# COBConnector.net
KiCad netlist of a schematic drawn in Altium Designer
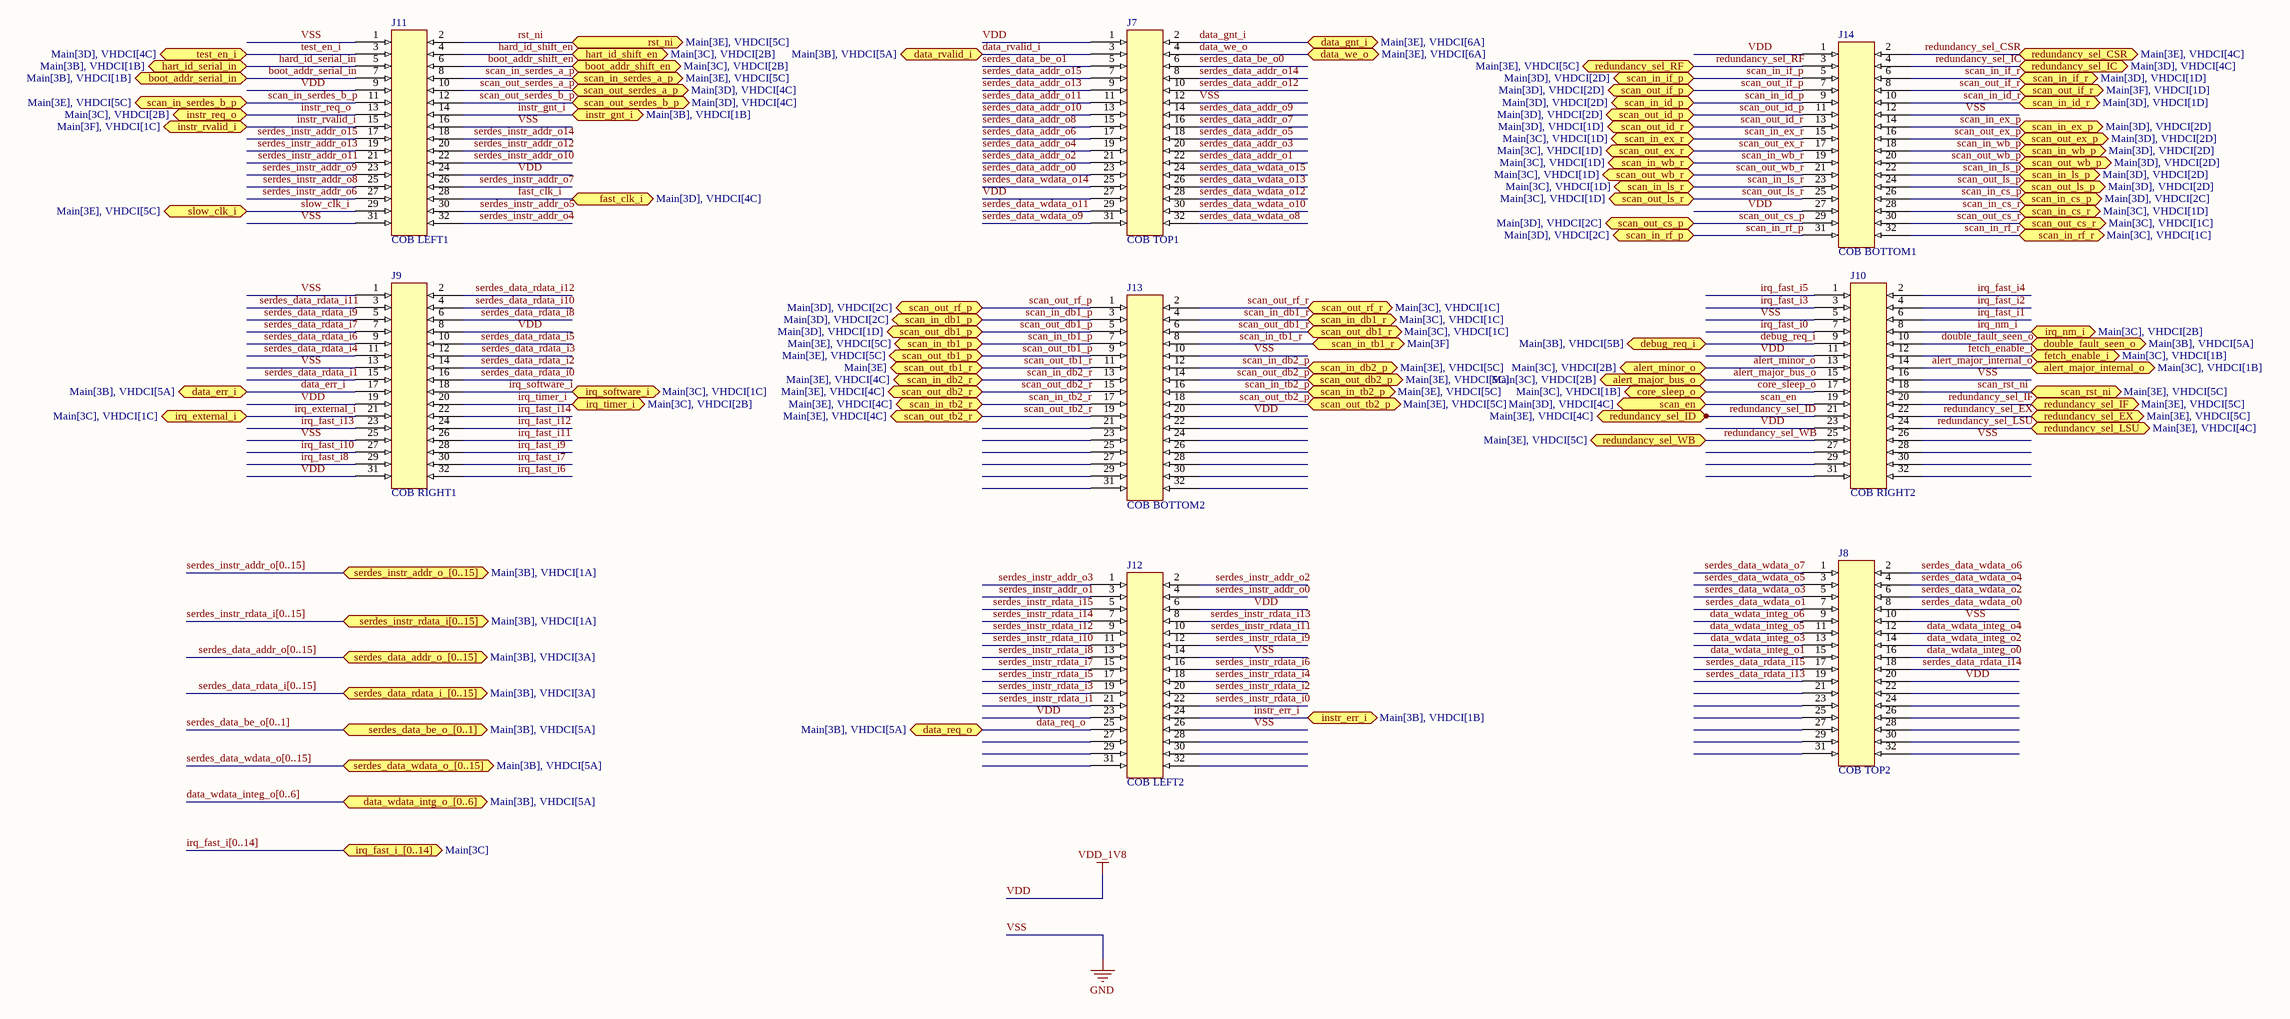
[diagram p0: COBConnector.SchDoc]

(export (version "E")
  (design (tool "Eeschema 10.0.6"))
  (components
    (comp (ref "J7")
      (value "COB TOP1")
      (footprint "CON32_2X16_TU_BBS_SAI")
      (libsource (lib "00-100001-001") (part "BBD-116-G-A"))
    )
    (comp (ref "J8")
      (value "COB TOP2")
      (footprint "CON32_2X16_TU_BBS_SAI")
      (libsource (lib "00-100001-001") (part "BBD-116-G-A"))
    )
    (comp (ref "J9")
      (value "COB RIGHT1")
      (footprint "CON32_2X16_TU_BBS_SAI")
      (libsource (lib "00-100001-001") (part "BBD-116-G-A"))
    )
    (comp (ref "J10")
      (value "COB RIGHT2")
      (footprint "CON32_2X16_TU_BBS_SAI")
      (libsource (lib "00-100001-001") (part "BBD-116-G-A"))
    )
    (comp (ref "J11")
      (value "COB LEFT1")
      (footprint "CON32_2X16_TU_BBS_SAI")
      (libsource (lib "00-100001-001") (part "BBD-116-G-A"))
    )
    (comp (ref "J12")
      (value "COB LEFT2")
      (footprint "CON32_2X16_TU_BBS_SAI")
      (libsource (lib "00-100001-001") (part "BBD-116-G-A"))
    )
    (comp (ref "J13")
      (value "COB BOTTOM2")
      (footprint "CON32_2X16_TU_BBS_SAI")
      (libsource (lib "00-100001-001") (part "BBD-116-G-A"))
    )
    (comp (ref "J14")
      (value "COB BOTTOM1")
      (footprint "CON32_2X16_TU_BBS_SAI")
      (libsource (lib "00-100001-001") (part "BBD-116-G-A"))
    )
  )
  (nets
    (net (code "1") (name "/alert_major_bus_o") (class "Default")
      (node (ref "J10") (pin "15") (pintype "input"))
    )
    (net (code "2") (name "/alert_major_internal_o") (class "Default")
      (node (ref "J10") (pin "14") (pintype "input"))
    )
    (net (code "3") (name "/alert_minor_o") (class "Default") (node (ref "J10") (pin "13") (pintype "input")))
    (net (code "4") (name "/boot_addr_serial_in") (class "Default")
      (node (ref "J11") (pin "7") (pintype "input"))
    )
    (net (code "5") (name "/boot_addr_shift_en") (class "Default")
      (node (ref "J11") (pin "6") (pintype "input"))
    )
    (net (code "6") (name "/core_sleep_o") (class "Default") (node (ref "J10") (pin "17") (pintype "input")))
    (net (code "7") (name "/data_err_i") (class "Default") (node (ref "J9") (pin "17") (pintype "input")))
    (net (code "8") (name "/data_gnt_i") (class "Default") (node (ref "J7") (pin "2") (pintype "input")))
    (net (code "9") (name "/data_req_o") (class "Default") (node (ref "J12") (pin "25") (pintype "input")))
    (net (code "10") (name "/data_rvalid_i") (class "Default") (node (ref "J7") (pin "3") (pintype "input")))
    (net (code "11") (name "/data_wdata_integ_o0") (class "Default")
      (node (ref "J8") (pin "16") (pintype "input"))
    )
    (net (code "12") (name "/data_wdata_integ_o1") (class "Default")
      (node (ref "J8") (pin "15") (pintype "input"))
    )
    (net (code "13") (name "/data_wdata_integ_o2") (class "Default")
      (node (ref "J8") (pin "14") (pintype "input"))
    )
    (net (code "14") (name "/data_wdata_integ_o3") (class "Default")
      (node (ref "J8") (pin "13") (pintype "input"))
    )
    (net (code "15") (name "/data_wdata_integ_o4") (class "Default")
      (node (ref "J8") (pin "12") (pintype "input"))
    )
    (net (code "16") (name "/data_wdata_integ_o5") (class "Default")
      (node (ref "J8") (pin "11") (pintype "input"))
    )
    (net (code "17") (name "/data_wdata_integ_o6") (class "Default")
      (node (ref "J8") (pin "9") (pintype "input"))
    )
    (net (code "19") (name "/data_we_o") (class "Default") (node (ref "J7") (pin "4") (pintype "input")))
    (net (code "20") (name "/debug_req_i") (class "Default") (node (ref "J10") (pin "9") (pintype "input")))
    (net (code "21") (name "/double_fault_seen_o") (class "Default")
      (node (ref "J10") (pin "10") (pintype "input"))
    )
    (net (code "22") (name "/fast_clk_i") (class "Default") (node (ref "J11") (pin "28") (pintype "input")))
    (net (code "23") (name "/fetch_enable_i") (class "Default")
      (node (ref "J10") (pin "12") (pintype "input"))
    )
    (net (code "24") (name "/hard_id_serial_in") (class "Default")
      (node (ref "J11") (pin "5") (pintype "input"))
    )
    (net (code "25") (name "/hard_id_shift_en") (class "Default")
      (node (ref "J11") (pin "4") (pintype "input"))
    )
    (net (code "26") (name "/instr_err_i") (class "Default") (node (ref "J12") (pin "24") (pintype "input")))
    (net (code "27") (name "/instr_gnt_i") (class "Default") (node (ref "J11") (pin "14") (pintype "input")))
    (net (code "28") (name "/instr_req_o") (class "Default") (node (ref "J11") (pin "13") (pintype "input")))
    (net (code "29") (name "/instr_rvalid_i") (class "Default")
      (node (ref "J11") (pin "15") (pintype "input"))
    )
    (net (code "30") (name "/irq_external_i") (class "Default")
      (node (ref "J9") (pin "21") (pintype "input"))
    )
    (net (code "31") (name "/irq_fast_i0") (class "Default") (node (ref "J10") (pin "7") (pintype "input")))
    (net (code "32") (name "/irq_fast_i1") (class "Default") (node (ref "J10") (pin "6") (pintype "input")))
    (net (code "33") (name "/irq_fast_i2") (class "Default") (node (ref "J10") (pin "4") (pintype "input")))
    (net (code "34") (name "/irq_fast_i3") (class "Default") (node (ref "J10") (pin "3") (pintype "input")))
    (net (code "35") (name "/irq_fast_i4") (class "Default") (node (ref "J10") (pin "2") (pintype "input")))
    (net (code "36") (name "/irq_fast_i5") (class "Default") (node (ref "J10") (pin "1") (pintype "input")))
    (net (code "37") (name "/irq_fast_i6") (class "Default") (node (ref "J9") (pin "32") (pintype "input")))
    (net (code "38") (name "/irq_fast_i7") (class "Default") (node (ref "J9") (pin "30") (pintype "input")))
    (net (code "39") (name "/irq_fast_i8") (class "Default") (node (ref "J9") (pin "29") (pintype "input")))
    (net (code "40") (name "/irq_fast_i9") (class "Default") (node (ref "J9") (pin "28") (pintype "input")))
    (net (code "41") (name "/irq_fast_i10") (class "Default") (node (ref "J9") (pin "27") (pintype "input")))
    (net (code "42") (name "/irq_fast_i11") (class "Default") (node (ref "J9") (pin "26") (pintype "input")))
    (net (code "43") (name "/irq_fast_i12") (class "Default") (node (ref "J9") (pin "24") (pintype "input")))
    (net (code "44") (name "/irq_fast_i13") (class "Default") (node (ref "J9") (pin "23") (pintype "input")))
    (net (code "45") (name "/irq_fast_i14") (class "Default") (node (ref "J9") (pin "22") (pintype "input")))
    (net (code "47") (name "/irq_nm_i") (class "Default") (node (ref "J10") (pin "8") (pintype "input")))
    (net (code "48") (name "/irq_software_i") (class "Default")
      (node (ref "J9") (pin "18") (pintype "input"))
    )
    (net (code "49") (name "/irq_timer_i") (class "Default") (node (ref "J9") (pin "20") (pintype "input")))
    (net (code "50") (name "/redundancy_sel_CSR") (class "Default")
      (node (ref "J14") (pin "2") (pintype "input"))
    )
    (net (code "51") (name "/redundancy_sel_EX") (class "Default")
      (node (ref "J10") (pin "22") (pintype "input"))
    )
    (net (code "52") (name "/redundancy_sel_IC") (class "Default")
      (node (ref "J14") (pin "4") (pintype "input"))
    )
    (net (code "53") (name "/redundancy_sel_ID") (class "Default")
      (node (ref "J10") (pin "21") (pintype "input"))
    )
    (net (code "54") (name "/redundancy_sel_IF") (class "Default")
      (node (ref "J10") (pin "20") (pintype "input"))
    )
    (net (code "55") (name "/redundancy_sel_LSU") (class "Default")
      (node (ref "J10") (pin "24") (pintype "input"))
    )
    (net (code "56") (name "/redundancy_sel_RF") (class "Default")
      (node (ref "J14") (pin "3") (pintype "input"))
    )
    (net (code "57") (name "/redundancy_sel_WB") (class "Default")
      (node (ref "J10") (pin "25") (pintype "input"))
    )
    (net (code "58") (name "/rst_ni") (class "Default") (node (ref "J11") (pin "2") (pintype "input")))
    (net (code "59") (name "/scan_en") (class "Default") (node (ref "J10") (pin "19") (pintype "input")))
    (net (code "60") (name "/scan_in_cs_p") (class "Default") (node (ref "J14") (pin "26") (pintype "input")))
    (net (code "61") (name "/scan_in_cs_r") (class "Default") (node (ref "J14") (pin "28") (pintype "input")))
    (net (code "62") (name "/scan_in_db1_p") (class "Default") (node (ref "J13") (pin "3") (pintype "input")))
    (net (code "63") (name "/scan_in_db1_r") (class "Default") (node (ref "J13") (pin "4") (pintype "input")))
    (net (code "64") (name "/scan_in_db2_p") (class "Default")
      (node (ref "J13") (pin "12") (pintype "input"))
    )
    (net (code "65") (name "/scan_in_db2_r") (class "Default")
      (node (ref "J13") (pin "13") (pintype "input"))
    )
    (net (code "66") (name "/scan_in_ex_p") (class "Default") (node (ref "J14") (pin "14") (pintype "input")))
    (net (code "67") (name "/scan_in_ex_r") (class "Default") (node (ref "J14") (pin "15") (pintype "input")))
    (net (code "68") (name "/scan_in_id_p") (class "Default") (node (ref "J14") (pin "9") (pintype "input")))
    (net (code "69") (name "/scan_in_id_r") (class "Default") (node (ref "J14") (pin "10") (pintype "input")))
    (net (code "70") (name "/scan_in_if_p") (class "Default") (node (ref "J14") (pin "5") (pintype "input")))
    (net (code "71") (name "/scan_in_if_r") (class "Default") (node (ref "J14") (pin "6") (pintype "input")))
    (net (code "72") (name "/scan_in_ls_p") (class "Default") (node (ref "J14") (pin "22") (pintype "input")))
    (net (code "73") (name "/scan_in_ls_r") (class "Default") (node (ref "J14") (pin "23") (pintype "input")))
    (net (code "74") (name "/scan_in_rf_p") (class "Default") (node (ref "J14") (pin "31") (pintype "input")))
    (net (code "75") (name "/scan_in_rf_r") (class "Default") (node (ref "J14") (pin "32") (pintype "input")))
    (net (code "76") (name "/scan_in_serdes_a_p") (class "Default")
      (node (ref "J11") (pin "8") (pintype "input"))
    )
    (net (code "77") (name "/scan_in_serdes_b_p") (class "Default")
      (node (ref "J11") (pin "11") (pintype "input"))
    )
    (net (code "78") (name "/scan_in_tb1_p") (class "Default") (node (ref "J13") (pin "7") (pintype "input")))
    (net (code "79") (name "/scan_in_tb1_r") (class "Default") (node (ref "J13") (pin "8") (pintype "input")))
    (net (code "80") (name "/scan_in_tb2_p") (class "Default")
      (node (ref "J13") (pin "16") (pintype "input"))
    )
    (net (code "81") (name "/scan_in_tb2_r") (class "Default")
      (node (ref "J13") (pin "17") (pintype "input"))
    )
    (net (code "82") (name "/scan_in_wb_p") (class "Default") (node (ref "J14") (pin "18") (pintype "input")))
    (net (code "83") (name "/scan_in_wb_r") (class "Default") (node (ref "J14") (pin "19") (pintype "input")))
    (net (code "84") (name "/scan_out_cs_p") (class "Default")
      (node (ref "J14") (pin "29") (pintype "input"))
    )
    (net (code "85") (name "/scan_out_cs_r") (class "Default")
      (node (ref "J14") (pin "30") (pintype "input"))
    )
    (net (code "86") (name "/scan_out_db1_p") (class "Default")
      (node (ref "J13") (pin "5") (pintype "input"))
    )
    (net (code "87") (name "/scan_out_db1_r") (class "Default")
      (node (ref "J13") (pin "6") (pintype "input"))
    )
    (net (code "88") (name "/scan_out_db2_p") (class "Default")
      (node (ref "J13") (pin "14") (pintype "input"))
    )
    (net (code "89") (name "/scan_out_db2_r") (class "Default")
      (node (ref "J13") (pin "15") (pintype "input"))
    )
    (net (code "90") (name "/scan_out_ex_p") (class "Default")
      (node (ref "J14") (pin "16") (pintype "input"))
    )
    (net (code "91") (name "/scan_out_ex_r") (class "Default")
      (node (ref "J14") (pin "17") (pintype "input"))
    )
    (net (code "92") (name "/scan_out_id_p") (class "Default")
      (node (ref "J14") (pin "11") (pintype "input"))
    )
    (net (code "93") (name "/scan_out_id_r") (class "Default")
      (node (ref "J14") (pin "13") (pintype "input"))
    )
    (net (code "94") (name "/scan_out_if_p") (class "Default") (node (ref "J14") (pin "7") (pintype "input")))
    (net (code "95") (name "/scan_out_if_r") (class "Default") (node (ref "J14") (pin "8") (pintype "input")))
    (net (code "96") (name "/scan_out_ls_p") (class "Default")
      (node (ref "J14") (pin "24") (pintype "input"))
    )
    (net (code "97") (name "/scan_out_ls_r") (class "Default")
      (node (ref "J14") (pin "25") (pintype "input"))
    )
    (net (code "98") (name "/scan_out_rf_p") (class "Default") (node (ref "J13") (pin "1") (pintype "input")))
    (net (code "99") (name "/scan_out_rf_r") (class "Default") (node (ref "J13") (pin "2") (pintype "input")))
    (net (code "100") (name "/scan_out_serdes_a_p") (class "Default")
      (node (ref "J11") (pin "10") (pintype "input"))
    )
    (net (code "101") (name "/scan_out_serdes_b_p") (class "Default")
      (node (ref "J11") (pin "12") (pintype "input"))
    )
    (net (code "102") (name "/scan_out_tb1_p") (class "Default")
      (node (ref "J13") (pin "9") (pintype "input"))
    )
    (net (code "103") (name "/scan_out_tb1_r") (class "Default")
      (node (ref "J13") (pin "11") (pintype "input"))
    )
    (net (code "104") (name "/scan_out_tb2_p") (class "Default")
      (node (ref "J13") (pin "18") (pintype "input"))
    )
    (net (code "105") (name "/scan_out_tb2_r") (class "Default")
      (node (ref "J13") (pin "19") (pintype "input"))
    )
    (net (code "106") (name "/scan_out_wb_p") (class "Default")
      (node (ref "J14") (pin "20") (pintype "input"))
    )
    (net (code "107") (name "/scan_out_wb_r") (class "Default")
      (node (ref "J14") (pin "21") (pintype "input"))
    )
    (net (code "108") (name "/scan_rst_ni") (class "Default") (node (ref "J10") (pin "18") (pintype "input")))
    (net (code "109") (name "/serdes_data_addr_o0") (class "Default")
      (node (ref "J7") (pin "23") (pintype "input"))
    )
    (net (code "110") (name "/serdes_data_addr_o1") (class "Default")
      (node (ref "J7") (pin "22") (pintype "input"))
    )
    (net (code "111") (name "/serdes_data_addr_o2") (class "Default")
      (node (ref "J7") (pin "21") (pintype "input"))
    )
    (net (code "112") (name "/serdes_data_addr_o3") (class "Default")
      (node (ref "J7") (pin "20") (pintype "input"))
    )
    (net (code "113") (name "/serdes_data_addr_o4") (class "Default")
      (node (ref "J7") (pin "19") (pintype "input"))
    )
    (net (code "114") (name "/serdes_data_addr_o5") (class "Default")
      (node (ref "J7") (pin "18") (pintype "input"))
    )
    (net (code "115") (name "/serdes_data_addr_o6") (class "Default")
      (node (ref "J7") (pin "17") (pintype "input"))
    )
    (net (code "116") (name "/serdes_data_addr_o7") (class "Default")
      (node (ref "J7") (pin "16") (pintype "input"))
    )
    (net (code "117") (name "/serdes_data_addr_o8") (class "Default")
      (node (ref "J7") (pin "15") (pintype "input"))
    )
    (net (code "118") (name "/serdes_data_addr_o9") (class "Default")
      (node (ref "J7") (pin "14") (pintype "input"))
    )
    (net (code "119") (name "/serdes_data_addr_o10") (class "Default")
      (node (ref "J7") (pin "13") (pintype "input"))
    )
    (net (code "120") (name "/serdes_data_addr_o11") (class "Default")
      (node (ref "J7") (pin "11") (pintype "input"))
    )
    (net (code "121") (name "/serdes_data_addr_o12") (class "Default")
      (node (ref "J7") (pin "10") (pintype "input"))
    )
    (net (code "122") (name "/serdes_data_addr_o13") (class "Default")
      (node (ref "J7") (pin "9") (pintype "input"))
    )
    (net (code "123") (name "/serdes_data_addr_o14") (class "Default")
      (node (ref "J7") (pin "8") (pintype "input"))
    )
    (net (code "124") (name "/serdes_data_addr_o15") (class "Default")
      (node (ref "J7") (pin "7") (pintype "input"))
    )
    (net (code "126") (name "/serdes_data_be_o0") (class "Default")
      (node (ref "J7") (pin "6") (pintype "input"))
    )
    (net (code "127") (name "/serdes_data_be_o1") (class "Default")
      (node (ref "J7") (pin "5") (pintype "input"))
    )
    (net (code "129") (name "/serdes_data_rdata_i0") (class "Default")
      (node (ref "J9") (pin "16") (pintype "input"))
    )
    (net (code "130") (name "/serdes_data_rdata_i1") (class "Default")
      (node (ref "J9") (pin "15") (pintype "input"))
    )
    (net (code "131") (name "/serdes_data_rdata_i2") (class "Default")
      (node (ref "J9") (pin "14") (pintype "input"))
    )
    (net (code "132") (name "/serdes_data_rdata_i3") (class "Default")
      (node (ref "J9") (pin "12") (pintype "input"))
    )
    (net (code "133") (name "/serdes_data_rdata_i4") (class "Default")
      (node (ref "J9") (pin "11") (pintype "input"))
    )
    (net (code "134") (name "/serdes_data_rdata_i5") (class "Default")
      (node (ref "J9") (pin "10") (pintype "input"))
    )
    (net (code "135") (name "/serdes_data_rdata_i6") (class "Default")
      (node (ref "J9") (pin "9") (pintype "input"))
    )
    (net (code "136") (name "/serdes_data_rdata_i7") (class "Default")
      (node (ref "J9") (pin "7") (pintype "input"))
    )
    (net (code "137") (name "/serdes_data_rdata_i8") (class "Default")
      (node (ref "J9") (pin "6") (pintype "input"))
    )
    (net (code "138") (name "/serdes_data_rdata_i9") (class "Default")
      (node (ref "J9") (pin "5") (pintype "input"))
    )
    (net (code "139") (name "/serdes_data_rdata_i10") (class "Default")
      (node (ref "J9") (pin "4") (pintype "input"))
    )
    (net (code "140") (name "/serdes_data_rdata_i11") (class "Default")
      (node (ref "J9") (pin "3") (pintype "input"))
    )
    (net (code "141") (name "/serdes_data_rdata_i12") (class "Default")
      (node (ref "J9") (pin "2") (pintype "input"))
    )
    (net (code "142") (name "/serdes_data_rdata_i13") (class "Default")
      (node (ref "J8") (pin "19") (pintype "input"))
    )
    (net (code "143") (name "/serdes_data_rdata_i14") (class "Default")
      (node (ref "J8") (pin "18") (pintype "input"))
    )
    (net (code "144") (name "/serdes_data_rdata_i15") (class "Default")
      (node (ref "J8") (pin "17") (pintype "input"))
    )
    (net (code "146") (name "/serdes_data_wdata_o0") (class "Default")
      (node (ref "J8") (pin "8") (pintype "input"))
    )
    (net (code "147") (name "/serdes_data_wdata_o1") (class "Default")
      (node (ref "J8") (pin "7") (pintype "input"))
    )
    (net (code "148") (name "/serdes_data_wdata_o2") (class "Default")
      (node (ref "J8") (pin "6") (pintype "input"))
    )
    (net (code "149") (name "/serdes_data_wdata_o3") (class "Default")
      (node (ref "J8") (pin "5") (pintype "input"))
    )
    (net (code "150") (name "/serdes_data_wdata_o4") (class "Default")
      (node (ref "J8") (pin "4") (pintype "input"))
    )
    (net (code "151") (name "/serdes_data_wdata_o5") (class "Default")
      (node (ref "J8") (pin "3") (pintype "input"))
    )
    (net (code "152") (name "/serdes_data_wdata_o6") (class "Default")
      (node (ref "J8") (pin "2") (pintype "input"))
    )
    (net (code "153") (name "/serdes_data_wdata_o7") (class "Default")
      (node (ref "J8") (pin "1") (pintype "input"))
    )
    (net (code "154") (name "/serdes_data_wdata_o8") (class "Default")
      (node (ref "J7") (pin "32") (pintype "input"))
    )
    (net (code "155") (name "/serdes_data_wdata_o9") (class "Default")
      (node (ref "J7") (pin "31") (pintype "input"))
    )
    (net (code "156") (name "/serdes_data_wdata_o10") (class "Default")
      (node (ref "J7") (pin "30") (pintype "input"))
    )
    (net (code "157") (name "/serdes_data_wdata_o11") (class "Default")
      (node (ref "J7") (pin "29") (pintype "input"))
    )
    (net (code "158") (name "/serdes_data_wdata_o12") (class "Default")
      (node (ref "J7") (pin "28") (pintype "input"))
    )
    (net (code "159") (name "/serdes_data_wdata_o13") (class "Default")
      (node (ref "J7") (pin "26") (pintype "input"))
    )
    (net (code "160") (name "/serdes_data_wdata_o14") (class "Default")
      (node (ref "J7") (pin "25") (pintype "input"))
    )
    (net (code "161") (name "/serdes_data_wdata_o15") (class "Default")
      (node (ref "J7") (pin "24") (pintype "input"))
    )
    (net (code "163") (name "/serdes_instr_addr_o0") (class "Default")
      (node (ref "J12") (pin "4") (pintype "input"))
    )
    (net (code "164") (name "/serdes_instr_addr_o1") (class "Default")
      (node (ref "J12") (pin "3") (pintype "input"))
    )
    (net (code "165") (name "/serdes_instr_addr_o2") (class "Default")
      (node (ref "J12") (pin "2") (pintype "input"))
    )
    (net (code "166") (name "/serdes_instr_addr_o3") (class "Default")
      (node (ref "J12") (pin "1") (pintype "input"))
    )
    (net (code "167") (name "/serdes_instr_addr_o4") (class "Default")
      (node (ref "J11") (pin "32") (pintype "input"))
    )
    (net (code "168") (name "/serdes_instr_addr_o5") (class "Default")
      (node (ref "J11") (pin "30") (pintype "input"))
    )
    (net (code "169") (name "/serdes_instr_addr_o6") (class "Default")
      (node (ref "J11") (pin "27") (pintype "input"))
    )
    (net (code "170") (name "/serdes_instr_addr_o7") (class "Default")
      (node (ref "J11") (pin "26") (pintype "input"))
    )
    (net (code "171") (name "/serdes_instr_addr_o8") (class "Default")
      (node (ref "J11") (pin "25") (pintype "input"))
    )
    (net (code "172") (name "/serdes_instr_addr_o9") (class "Default")
      (node (ref "J11") (pin "23") (pintype "input"))
    )
    (net (code "173") (name "/serdes_instr_addr_o10") (class "Default")
      (node (ref "J11") (pin "22") (pintype "input"))
    )
    (net (code "174") (name "/serdes_instr_addr_o11") (class "Default")
      (node (ref "J11") (pin "21") (pintype "input"))
    )
    (net (code "175") (name "/serdes_instr_addr_o12") (class "Default")
      (node (ref "J11") (pin "20") (pintype "input"))
    )
    (net (code "176") (name "/serdes_instr_addr_o13") (class "Default")
      (node (ref "J11") (pin "19") (pintype "input"))
    )
    (net (code "177") (name "/serdes_instr_addr_o14") (class "Default")
      (node (ref "J11") (pin "18") (pintype "input"))
    )
    (net (code "178") (name "/serdes_instr_addr_o15") (class "Default")
      (node (ref "J11") (pin "17") (pintype "input"))
    )
    (net (code "180") (name "/serdes_instr_rdata_i0") (class "Default")
      (node (ref "J12") (pin "22") (pintype "input"))
    )
    (net (code "181") (name "/serdes_instr_rdata_i1") (class "Default")
      (node (ref "J12") (pin "21") (pintype "input"))
    )
    (net (code "182") (name "/serdes_instr_rdata_i2") (class "Default")
      (node (ref "J12") (pin "20") (pintype "input"))
    )
    (net (code "183") (name "/serdes_instr_rdata_i3") (class "Default")
      (node (ref "J12") (pin "19") (pintype "input"))
    )
    (net (code "184") (name "/serdes_instr_rdata_i4") (class "Default")
      (node (ref "J12") (pin "18") (pintype "input"))
    )
    (net (code "185") (name "/serdes_instr_rdata_i5") (class "Default")
      (node (ref "J12") (pin "17") (pintype "input"))
    )
    (net (code "186") (name "/serdes_instr_rdata_i6") (class "Default")
      (node (ref "J12") (pin "16") (pintype "input"))
    )
    (net (code "187") (name "/serdes_instr_rdata_i7") (class "Default")
      (node (ref "J12") (pin "15") (pintype "input"))
    )
    (net (code "188") (name "/serdes_instr_rdata_i8") (class "Default")
      (node (ref "J12") (pin "13") (pintype "input"))
    )
    (net (code "189") (name "/serdes_instr_rdata_i9") (class "Default")
      (node (ref "J12") (pin "12") (pintype "input"))
    )
    (net (code "190") (name "/serdes_instr_rdata_i10") (class "Default")
      (node (ref "J12") (pin "11") (pintype "input"))
    )
    (net (code "191") (name "/serdes_instr_rdata_i11") (class "Default")
      (node (ref "J12") (pin "10") (pintype "input"))
    )
    (net (code "192") (name "/serdes_instr_rdata_i12") (class "Default")
      (node (ref "J12") (pin "9") (pintype "input"))
    )
    (net (code "193") (name "/serdes_instr_rdata_i13") (class "Default")
      (node (ref "J12") (pin "8") (pintype "input"))
    )
    (net (code "194") (name "/serdes_instr_rdata_i14") (class "Default")
      (node (ref "J12") (pin "7") (pintype "input"))
    )
    (net (code "195") (name "/serdes_instr_rdata_i15") (class "Default")
      (node (ref "J12") (pin "5") (pintype "input"))
    )
    (net (code "197") (name "/slow_clk_i") (class "Default") (node (ref "J11") (pin "29") (pintype "input")))
    (net (code "198") (name "/test_en_i") (class "Default") (node (ref "J11") (pin "3") (pintype "input")))
    (net (code "199") (name "GND") (class "Default")
      (node (ref "J10") (pin "16") (pintype "input"))
      (node (ref "J10") (pin "26") (pintype "input"))
      (node (ref "J10") (pin "5") (pintype "input"))
      (node (ref "J11") (pin "1") (pintype "input"))
      (node (ref "J11") (pin "16") (pintype "input"))
      (node (ref "J11") (pin "31") (pintype "input"))
      (node (ref "J12") (pin "14") (pintype "input"))
      (node (ref "J12") (pin "26") (pintype "input"))
      (node (ref "J13") (pin "10") (pintype "input"))
      (node (ref "J14") (pin "12") (pintype "input"))
      (node (ref "J7") (pin "12") (pintype "input"))
      (node (ref "J8") (pin "10") (pintype "input"))
      (node (ref "J9") (pin "1") (pintype "input"))
      (node (ref "J9") (pin "13") (pintype "input"))
      (node (ref "J9") (pin "25") (pintype "input"))
    )
    (net (code "200") (name "VDD_1V8") (class "Default")
      (node (ref "J10") (pin "11") (pintype "input"))
      (node (ref "J10") (pin "23") (pintype "input"))
      (node (ref "J11") (pin "24") (pintype "input"))
      (node (ref "J11") (pin "9") (pintype "input"))
      (node (ref "J12") (pin "23") (pintype "input"))
      (node (ref "J12") (pin "6") (pintype "input"))
      (node (ref "J13") (pin "20") (pintype "input"))
      (node (ref "J14") (pin "1") (pintype "input"))
      (node (ref "J14") (pin "27") (pintype "input"))
      (node (ref "J7") (pin "1") (pintype "input"))
      (node (ref "J7") (pin "27") (pintype "input"))
      (node (ref "J8") (pin "20") (pintype "input"))
      (node (ref "J9") (pin "19") (pintype "input"))
      (node (ref "J9") (pin "31") (pintype "input"))
      (node (ref "J9") (pin "8") (pintype "input"))
    )
    (net (code "201") (name "unconnected-(J8-Pad21)") (class "Default")
      (node (ref "J8") (pin "21") (pintype "input"))
    )
    (net (code "202") (name "unconnected-(J8-Pad22)") (class "Default")
      (node (ref "J8") (pin "22") (pintype "input"))
    )
    (net (code "203") (name "unconnected-(J8-Pad23)") (class "Default")
      (node (ref "J8") (pin "23") (pintype "input"))
    )
    (net (code "204") (name "unconnected-(J8-Pad24)") (class "Default")
      (node (ref "J8") (pin "24") (pintype "input"))
    )
    (net (code "205") (name "unconnected-(J8-Pad25)") (class "Default")
      (node (ref "J8") (pin "25") (pintype "input"))
    )
    (net (code "206") (name "unconnected-(J8-Pad26)") (class "Default")
      (node (ref "J8") (pin "26") (pintype "input"))
    )
    (net (code "207") (name "unconnected-(J8-Pad27)") (class "Default")
      (node (ref "J8") (pin "27") (pintype "input"))
    )
    (net (code "208") (name "unconnected-(J8-Pad28)") (class "Default")
      (node (ref "J8") (pin "28") (pintype "input"))
    )
    (net (code "209") (name "unconnected-(J8-Pad29)") (class "Default")
      (node (ref "J8") (pin "29") (pintype "input"))
    )
    (net (code "210") (name "unconnected-(J8-Pad30)") (class "Default")
      (node (ref "J8") (pin "30") (pintype "input"))
    )
    (net (code "211") (name "unconnected-(J8-Pad31)") (class "Default")
      (node (ref "J8") (pin "31") (pintype "input"))
    )
    (net (code "212") (name "unconnected-(J8-Pad32)") (class "Default")
      (node (ref "J8") (pin "32") (pintype "input"))
    )
    (net (code "213") (name "unconnected-(J10-Pad27)") (class "Default")
      (node (ref "J10") (pin "27") (pintype "input"))
    )
    (net (code "214") (name "unconnected-(J10-Pad28)") (class "Default")
      (node (ref "J10") (pin "28") (pintype "input"))
    )
    (net (code "215") (name "unconnected-(J10-Pad29)") (class "Default")
      (node (ref "J10") (pin "29") (pintype "input"))
    )
    (net (code "216") (name "unconnected-(J10-Pad30)") (class "Default")
      (node (ref "J10") (pin "30") (pintype "input"))
    )
    (net (code "217") (name "unconnected-(J10-Pad31)") (class "Default")
      (node (ref "J10") (pin "31") (pintype "input"))
    )
    (net (code "218") (name "unconnected-(J10-Pad32)") (class "Default")
      (node (ref "J10") (pin "32") (pintype "input"))
    )
    (net (code "219") (name "unconnected-(J12-Pad27)") (class "Default")
      (node (ref "J12") (pin "27") (pintype "input"))
    )
    (net (code "220") (name "unconnected-(J12-Pad28)") (class "Default")
      (node (ref "J12") (pin "28") (pintype "input"))
    )
    (net (code "221") (name "unconnected-(J12-Pad29)") (class "Default")
      (node (ref "J12") (pin "29") (pintype "input"))
    )
    (net (code "222") (name "unconnected-(J12-Pad30)") (class "Default")
      (node (ref "J12") (pin "30") (pintype "input"))
    )
    (net (code "223") (name "unconnected-(J12-Pad31)") (class "Default")
      (node (ref "J12") (pin "31") (pintype "input"))
    )
    (net (code "224") (name "unconnected-(J12-Pad32)") (class "Default")
      (node (ref "J12") (pin "32") (pintype "input"))
    )
    (net (code "225") (name "unconnected-(J13-Pad21)") (class "Default")
      (node (ref "J13") (pin "21") (pintype "input"))
    )
    (net (code "226") (name "unconnected-(J13-Pad22)") (class "Default")
      (node (ref "J13") (pin "22") (pintype "input"))
    )
    (net (code "227") (name "unconnected-(J13-Pad23)") (class "Default")
      (node (ref "J13") (pin "23") (pintype "input"))
    )
    (net (code "228") (name "unconnected-(J13-Pad24)") (class "Default")
      (node (ref "J13") (pin "24") (pintype "input"))
    )
    (net (code "229") (name "unconnected-(J13-Pad25)") (class "Default")
      (node (ref "J13") (pin "25") (pintype "input"))
    )
    (net (code "230") (name "unconnected-(J13-Pad26)") (class "Default")
      (node (ref "J13") (pin "26") (pintype "input"))
    )
    (net (code "231") (name "unconnected-(J13-Pad27)") (class "Default")
      (node (ref "J13") (pin "27") (pintype "input"))
    )
    (net (code "232") (name "unconnected-(J13-Pad28)") (class "Default")
      (node (ref "J13") (pin "28") (pintype "input"))
    )
    (net (code "233") (name "unconnected-(J13-Pad29)") (class "Default")
      (node (ref "J13") (pin "29") (pintype "input"))
    )
    (net (code "234") (name "unconnected-(J13-Pad30)") (class "Default")
      (node (ref "J13") (pin "30") (pintype "input"))
    )
    (net (code "235") (name "unconnected-(J13-Pad31)") (class "Default")
      (node (ref "J13") (pin "31") (pintype "input"))
    )
    (net (code "236") (name "unconnected-(J13-Pad32)") (class "Default")
      (node (ref "J13") (pin "32") (pintype "input"))
    )
  )
)
